# Pre-Amp_2017.net
KiCad netlist of a schematic drawn in Altium Designer
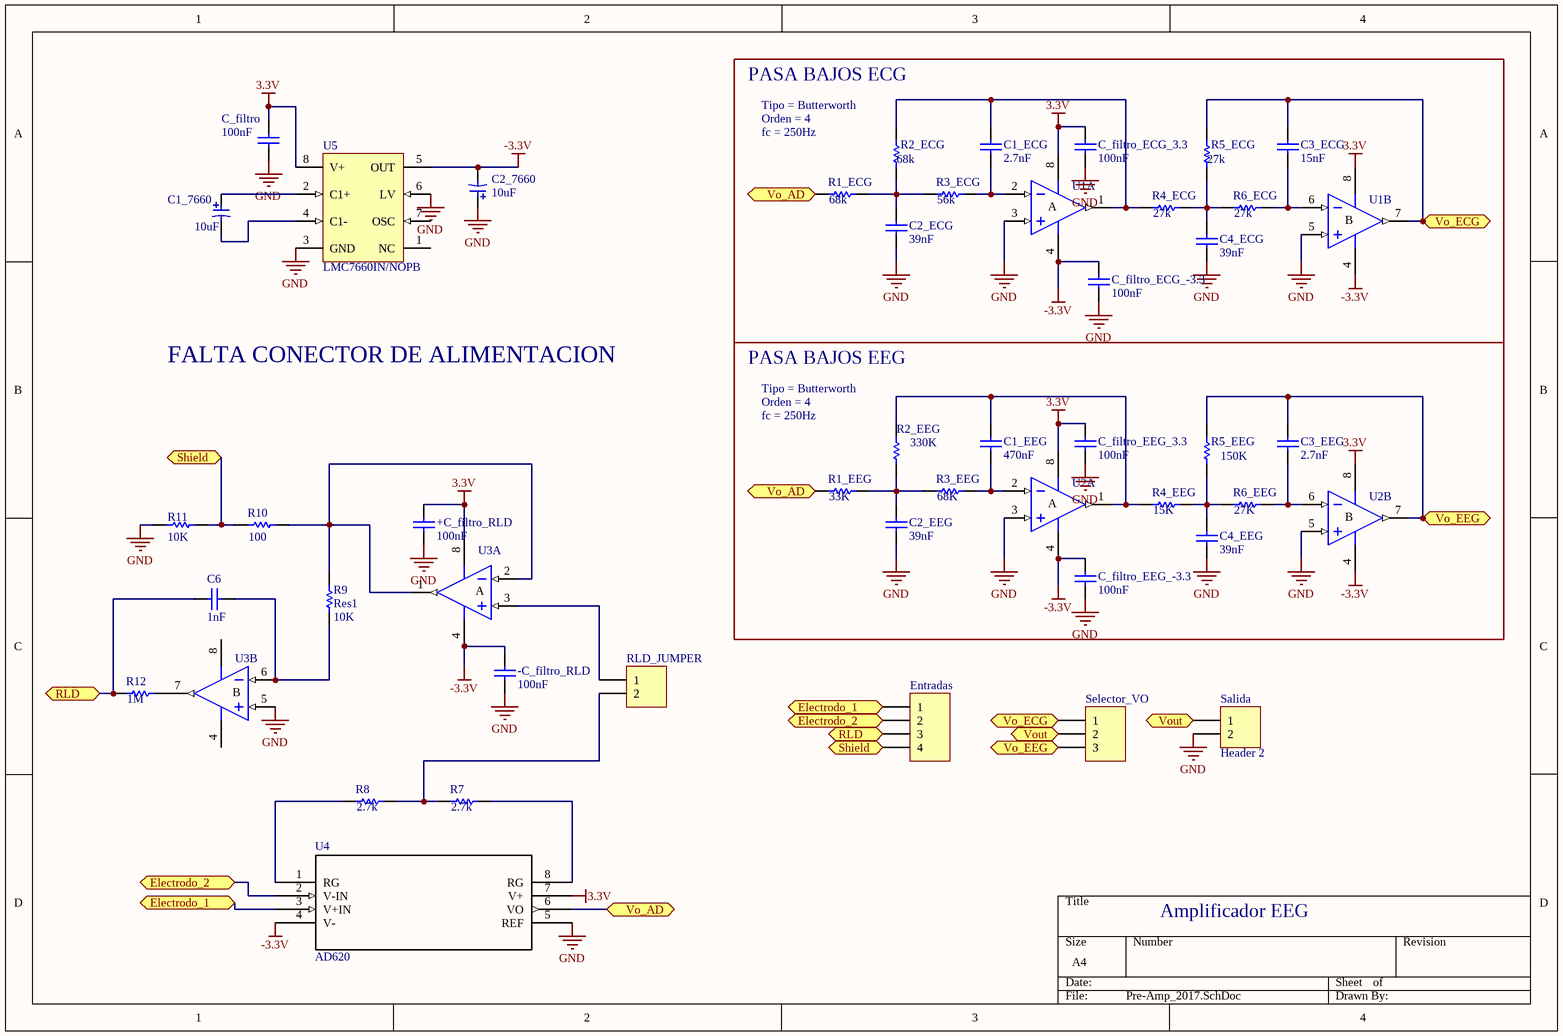
[diagram p0: Pre-Amp_2017.SchDoc]

(export (version "E")
  (design (tool "Eeschema 10.0.6"))
  (components
    (comp (ref "+C_filtro_RLD")
      (value "100nF")
      (footprint "VP40")
      (description "Dipped Radial Multilayer Ceramic Capacitor COG (NPO): 180pF, 50/63V")
      (fields (field (name "PUBLISHER") "Altium Limited"))
      (libsource (lib "Vishay Vitramon Ceramic Dipped Capacitor") (part "VP40BA181KA"))
    )
    (comp (ref "-C_filtro_RLD")
      (value "100nF")
      (footprint "VP40")
      (description "Dipped Radial Multilayer Ceramic Capacitor COG (NPO): 180pF, 50/63V")
      (fields (field (name "PUBLISHER") "Altium Limited"))
      (libsource (lib "Vishay Vitramon Ceramic Dipped Capacitor") (part "VP40BA181KA"))
    )
    (comp (ref "C1_7660")
      (value "10uF")
      (footprint "C Elec TH V 4x7-2.5")
      (description "Capacitor, polarized, generic")
      (fields (field (name "Comment") "C Pol"))
      (libsource (lib "IFS_Altium") (part "C Pol"))
    )
    (comp (ref "C1_ECG")
      (value "2.7nF")
      (footprint "VP40")
      (description "Dipped Radial Multilayer Ceramic Capacitor COG (NPO): 180pF, 50/63V")
      (fields (field (name "PUBLISHER") "Altium Limited"))
      (libsource (lib "Vishay Vitramon Ceramic Dipped Capacitor") (part "VP40BA181KA"))
    )
    (comp (ref "C1_EEG")
      (value "470nF")
      (footprint "VP40")
      (description "Dipped Radial Multilayer Ceramic Capacitor COG (NPO): 180pF, 50/63V")
      (fields (field (name "PUBLISHER") "Altium Limited"))
      (libsource (lib "Vishay Vitramon Ceramic Dipped Capacitor") (part "VP40BA181KA"))
    )
    (comp (ref "C2_7660")
      (value "10uF")
      (footprint "C Elec TH V 4x7-2.5")
      (description "Capacitor, polarized, generic")
      (fields (field (name "Comment") "C Pol"))
      (libsource (lib "IFS_Altium") (part "C Pol"))
    )
    (comp (ref "C2_ECG")
      (value "39nF")
      (footprint "VP40")
      (description "Dipped Radial Multilayer Ceramic Capacitor COG (NPO): 180pF, 50/63V")
      (fields (field (name "PUBLISHER") "Altium Limited"))
      (libsource (lib "Vishay Vitramon Ceramic Dipped Capacitor") (part "VP40BA181KA"))
    )
    (comp (ref "C2_EEG")
      (value "39nF")
      (footprint "VP40")
      (description "Dipped Radial Multilayer Ceramic Capacitor COG (NPO): 180pF, 50/63V")
      (fields (field (name "PUBLISHER") "Altium Limited"))
      (libsource (lib "Vishay Vitramon Ceramic Dipped Capacitor") (part "VP40BA181KA"))
    )
    (comp (ref "C3_ECG")
      (value "15nF")
      (footprint "VP40")
      (description "Dipped Radial Multilayer Ceramic Capacitor COG (NPO): 180pF, 50/63V")
      (fields (field (name "PUBLISHER") "Altium Limited"))
      (libsource (lib "Vishay Vitramon Ceramic Dipped Capacitor") (part "VP40BA181KA"))
    )
    (comp (ref "C3_EEG")
      (value "2.7nF")
      (footprint "VP40")
      (description "Dipped Radial Multilayer Ceramic Capacitor COG (NPO): 180pF, 50/63V")
      (fields (field (name "PUBLISHER") "Altium Limited"))
      (libsource (lib "Vishay Vitramon Ceramic Dipped Capacitor") (part "VP40BA181KA"))
    )
    (comp (ref "C4_ECG")
      (value "39nF")
      (footprint "VP40")
      (description "Dipped Radial Multilayer Ceramic Capacitor COG (NPO): 180pF, 50/63V")
      (fields (field (name "PUBLISHER") "Altium Limited"))
      (libsource (lib "Vishay Vitramon Ceramic Dipped Capacitor") (part "VP40BA181KA"))
    )
    (comp (ref "C4_EEG")
      (value "39nF")
      (footprint "VP40")
      (description "Dipped Radial Multilayer Ceramic Capacitor COG (NPO): 180pF, 50/63V")
      (fields (field (name "PUBLISHER") "Altium Limited"))
      (libsource (lib "Vishay Vitramon Ceramic Dipped Capacitor") (part "VP40BA181KA"))
    )
    (comp (ref "C6")
      (value "1nF")
      (footprint "VP40")
      (description "Dipped Radial Multilayer Ceramic Capacitor COG (NPO): 180pF, 50/63V")
      (fields (field (name "PUBLISHER") "Altium Limited"))
      (libsource (lib "Vishay Vitramon Ceramic Dipped Capacitor") (part "VP40BA181KA"))
    )
    (comp (ref "C_filtro")
      (value "100nF")
      (footprint "VP31-3.2")
      (description "Dipped Radial Multilayer Ceramic Capacitor COG (NPO): 82pF, 200V")
      (fields (field (name "PUBLISHER") "Altium Limited"))
      (libsource (lib "Vishay Vitramon Ceramic Dipped Capacitor") (part "VP31BA820KC"))
    )
    (comp (ref "C_filtro_ECG_-3.3")
      (value "100nF")
      (footprint "VP40")
      (description "Dipped Radial Multilayer Ceramic Capacitor COG (NPO): 180pF, 50/63V")
      (fields (field (name "PUBLISHER") "Altium Limited"))
      (libsource (lib "Vishay Vitramon Ceramic Dipped Capacitor") (part "VP40BA181KA"))
    )
    (comp (ref "C_filtro_ECG_3.3")
      (value "100nF")
      (footprint "VP40")
      (description "Dipped Radial Multilayer Ceramic Capacitor COG (NPO): 180pF, 50/63V")
      (fields (field (name "PUBLISHER") "Altium Limited"))
      (libsource (lib "Vishay Vitramon Ceramic Dipped Capacitor") (part "VP40BA181KA"))
    )
    (comp (ref "C_filtro_EEG_-3.3")
      (value "100nF")
      (footprint "VP40")
      (description "Dipped Radial Multilayer Ceramic Capacitor COG (NPO): 180pF, 50/63V")
      (fields (field (name "PUBLISHER") "Altium Limited"))
      (libsource (lib "Vishay Vitramon Ceramic Dipped Capacitor") (part "VP40BA181KA"))
    )
    (comp (ref "C_filtro_EEG_3.3")
      (value "100nF")
      (footprint "VP40")
      (description "Dipped Radial Multilayer Ceramic Capacitor COG (NPO): 180pF, 50/63V")
      (fields (field (name "PUBLISHER") "Altium Limited"))
      (libsource (lib "Vishay Vitramon Ceramic Dipped Capacitor") (part "VP40BA181KA"))
    )
    (comp (ref "Entradas")
      (value "Header 4")
      (footprint "HDR1X4")
      (description "Header, 4-Pin")
      (fields (field (name "PUBLISHER") "Altium Limited"))
      (libsource (lib "Miscellaneous Connectors") (part "Header 4"))
    )
    (comp (ref "R1_ECG")
      (value "68k")
      (footprint "AXIAL-0.3")
      (description "Resistor")
      (fields (field (name "Comment") "Res1") (field (name "PUBLISHER") "Altium Limited"))
      (libsource (lib "Miscellaneous Devices") (part "Res1"))
    )
    (comp (ref "R1_EEG")
      (value "33K")
      (footprint "AXIAL-0.3")
      (description "Resistor")
      (fields (field (name "Comment") "Res1") (field (name "PUBLISHER") "Altium Limited"))
      (libsource (lib "Miscellaneous Devices") (part "Res1"))
    )
    (comp (ref "R2_ECG")
      (value "68k")
      (footprint "AXIAL-0.3")
      (description "Resistor")
      (fields (field (name "Comment") "Res1") (field (name "PUBLISHER") "Altium Limited"))
      (libsource (lib "Miscellaneous Devices") (part "Res1"))
    )
    (comp (ref "R2_EEG")
      (value "330K")
      (footprint "AXIAL-0.3")
      (description "Resistor")
      (fields (field (name "Comment") "Res1") (field (name "PUBLISHER") "Altium Limited"))
      (libsource (lib "Miscellaneous Devices") (part "Res1"))
    )
    (comp (ref "R3_ECG")
      (value "56k")
      (footprint "AXIAL-0.3")
      (description "Resistor")
      (fields (field (name "Comment") "Res1") (field (name "PUBLISHER") "Altium Limited"))
      (libsource (lib "Miscellaneous Devices") (part "Res1"))
    )
    (comp (ref "R3_EEG")
      (value "68K")
      (footprint "AXIAL-0.3")
      (description "Resistor")
      (fields (field (name "Comment") "Res1") (field (name "PUBLISHER") "Altium Limited"))
      (libsource (lib "Miscellaneous Devices") (part "Res1"))
    )
    (comp (ref "R4_ECG")
      (value "27k")
      (footprint "AXIAL-0.3")
      (description "Resistor")
      (fields (field (name "Comment") "Res1") (field (name "PUBLISHER") "Altium Limited"))
      (libsource (lib "Miscellaneous Devices") (part "Res1"))
    )
    (comp (ref "R4_EEG")
      (value "15K")
      (footprint "AXIAL-0.3")
      (description "Resistor")
      (fields (field (name "Comment") "Res1") (field (name "PUBLISHER") "Altium Limited"))
      (libsource (lib "Miscellaneous Devices") (part "Res1"))
    )
    (comp (ref "R5_ECG")
      (value "27k")
      (footprint "AXIAL-0.3")
      (description "Resistor")
      (fields (field (name "Comment") "Res1") (field (name "PUBLISHER") "Altium Limited"))
      (libsource (lib "Miscellaneous Devices") (part "Res1"))
    )
    (comp (ref "R5_EEG")
      (value "150K")
      (footprint "AXIAL-0.3")
      (description "Resistor")
      (fields (field (name "Comment") "Res1") (field (name "PUBLISHER") "Altium Limited"))
      (libsource (lib "Miscellaneous Devices") (part "Res1"))
    )
    (comp (ref "R6_ECG")
      (value "27k")
      (footprint "AXIAL-0.3")
      (description "Resistor")
      (fields (field (name "Comment") "Res1") (field (name "PUBLISHER") "Altium Limited"))
      (libsource (lib "Miscellaneous Devices") (part "Res1"))
    )
    (comp (ref "R6_EEG")
      (value "27K")
      (footprint "AXIAL-0.3")
      (description "Resistor")
      (fields (field (name "Comment") "Res1") (field (name "PUBLISHER") "Altium Limited"))
      (libsource (lib "Miscellaneous Devices") (part "Res1"))
    )
    (comp (ref "R7")
      (value "2.7k")
      (footprint "AXIAL-0.3")
      (description "Resistor")
      (fields (field (name "Comment") "Res1") (field (name "PUBLISHER") "Altium Limited"))
      (libsource (lib "Miscellaneous Devices") (part "Res1"))
    )
    (comp (ref "R8")
      (value "2.7k")
      (footprint "AXIAL-0.3")
      (description "Resistor")
      (fields (field (name "Comment") "Res1") (field (name "PUBLISHER") "Altium Limited"))
      (libsource (lib "Miscellaneous Devices") (part "Res1"))
    )
    (comp (ref "R9")
      (value "Res1")
      (footprint "AXIAL-0.3")
      (description "Resistor")
      (fields (field (name "ALTIUM_VALUE") "10K") (field (name "PUBLISHER") "Altium Limited"))
      (libsource (lib "Miscellaneous Devices") (part "Res1"))
    )
    (comp (ref "R10")
      (value "100")
      (footprint "AXIAL-0.3")
      (description "Resistor")
      (fields (field (name "PUBLISHER") "Altium Limited"))
      (libsource (lib "Miscellaneous Devices") (part "Res1"))
    )
    (comp (ref "R11")
      (value "10K")
      (footprint "AXIAL-0.3")
      (description "Resistor")
      (fields (field (name "Comment") "Res1") (field (name "PUBLISHER") "Altium Limited"))
      (libsource (lib "Miscellaneous Devices") (part "Res1"))
    )
    (comp (ref "R12")
      (value "1M")
      (footprint "AXIAL-0.3")
      (description "Resistor")
      (fields (field (name "Comment") "Res1") (field (name "PUBLISHER") "Altium Limited"))
      (libsource (lib "Miscellaneous Devices") (part "Res1"))
    )
    (comp (ref "RLD_JUMPER")
      (value "Header 2")
      (footprint "HDR1X2")
      (description "Header, 2-Pin")
      (fields (field (name "PUBLISHER") "Altium Limited"))
      (libsource (lib "Miscellaneous Connectors") (part "Header 2"))
    )
    (comp (ref "Salida")
      (value "Header 2")
      (footprint "HDR1X2")
      (description "Header, 2-Pin")
      (fields (field (name "PUBLISHER") "Altium Limited"))
      (libsource (lib "Miscellaneous Connectors") (part "Header 2"))
    )
    (comp (ref "Selector_VO")
      (value "Header 3")
      (footprint "HDR1X3")
      (description "Header, 3-Pin")
      (fields (field (name "PUBLISHER") "Altium Limited"))
      (libsource (lib "Miscellaneous Connectors") (part "Header 3"))
    )
    (comp (ref "U1")
      (value "LT1358CN8")
      (footprint "N8")
      (description "Dual 25MHz, 600V/µs Operational Amplifier")
      (fields (field (name "PUBLISHER") "Altium Limited"))
      (libsource (lib "LT Operational Amplifier") (part "LT1358CN8"))
    )
    (comp (ref "U2")
      (value "LT1358CN8")
      (footprint "N8")
      (description "Dual 25MHz, 600V/µs Operational Amplifier")
      (fields (field (name "PUBLISHER") "Altium Limited"))
      (libsource (lib "LT Operational Amplifier") (part "LT1358CN8"))
    )
    (comp (ref "U3")
      (value "LT1358CN8")
      (footprint "N8")
      (description "Dual 25MHz, 600V/µs Operational Amplifier")
      (fields (field (name "PUBLISHER") "Altium Limited"))
      (libsource (lib "LT Operational Amplifier") (part "LT1358CN8"))
    )
    (comp (ref "U4") (value "AD620") (footprint "DIP8") (libsource (lib "Lucas") (part "INA129")))
    (comp (ref "U5")
      (value "LMC7660IN/NOPB")
      (footprint "N08E")
      (description "Switched Capacitor Voltage Converter, 8-pin MDIP, Pb-Free")
      (fields (field (name "MANUFACTURER") "National Semiconductor"))
      (libsource (lib "National Semiconductor Switch Caps") (part "LMC7660IN/NOPB"))
    )
  )
  (nets
    (net (code "1") (name "-3.3V") (class "Default")
      (node (ref "-C_filtro_RLD") (pin "2") (pinfunction "2_2") (pintype "passive"))
      (node (ref "C2_7660") (pin "1") (pinfunction "1_1") (pintype "passive"))
      (node (ref "C_filtro_ECG_-3.3") (pin "2") (pinfunction "2_2") (pintype "passive"))
      (node (ref "C_filtro_EEG_-3.3") (pin "2") (pinfunction "2_2") (pintype "passive"))
      (node (ref "U1") (pin "4") (pinfunction "V-_4") (pintype "power_in"))
      (node (ref "U2") (pin "4") (pinfunction "V-_4") (pintype "power_in"))
      (node (ref "U3") (pin "4") (pinfunction "V-_4") (pintype "power_in"))
      (node (ref "U4") (pin "4") (pinfunction "V-_4") (pintype "power_in"))
      (node (ref "U5") (pin "5") (pinfunction "OUT_5") (pintype "power_in"))
    )
    (net (code "2") (name "/Electrodo_1") (class "Default")
      (node (ref "Entradas") (pin "1") (pinfunction "1_1") (pintype "passive"))
      (node (ref "U4") (pin "3") (pinfunction "V+IN_3") (pintype "input"))
    )
    (net (code "3") (name "/Electrodo_2") (class "Default")
      (node (ref "Entradas") (pin "2") (pinfunction "2_2") (pintype "passive"))
      (node (ref "U4") (pin "2") (pinfunction "V-IN_2") (pintype "input"))
    )
    (net (code "4") (name "/RLD") (class "Default")
      (node (ref "C6") (pin "1") (pinfunction "1_1") (pintype "passive"))
      (node (ref "Entradas") (pin "3") (pinfunction "3_3") (pintype "passive"))
      (node (ref "R12") (pin "2") (pinfunction "2_2") (pintype "passive"))
    )
    (net (code "5") (name "/Shield") (class "Default")
      (node (ref "Entradas") (pin "4") (pinfunction "4_4") (pintype "passive"))
      (node (ref "R10") (pin "2") (pinfunction "2_2") (pintype "passive"))
      (node (ref "R11") (pin "1") (pinfunction "1_1") (pintype "passive"))
    )
    (net (code "6") (name "/Vo_AD") (class "Default")
      (node (ref "R1_ECG") (pin "1") (pinfunction "1_1") (pintype "passive"))
      (node (ref "R1_EEG") (pin "1") (pinfunction "1_1") (pintype "passive"))
      (node (ref "U4") (pin "6") (pinfunction "VO_6") (pintype "output"))
    )
    (net (code "7") (name "/Vo_ECG") (class "Default")
      (node (ref "C3_ECG") (pin "2") (pinfunction "2_2") (pintype "passive"))
      (node (ref "R5_ECG") (pin "2") (pinfunction "2_2") (pintype "passive"))
      (node (ref "Selector_VO") (pin "1") (pinfunction "1_1") (pintype "passive"))
      (node (ref "U1") (pin "7") (pinfunction "OUT_7") (pintype "output"))
    )
    (net (code "8") (name "/Vo_EEG") (class "Default")
      (node (ref "C3_EEG") (pin "2") (pinfunction "2_2") (pintype "passive"))
      (node (ref "R5_EEG") (pin "2") (pinfunction "2_2") (pintype "passive"))
      (node (ref "Selector_VO") (pin "3") (pinfunction "3_3") (pintype "passive"))
      (node (ref "U2") (pin "7") (pinfunction "OUT_7") (pintype "output"))
    )
    (net (code "9") (name "/Vout") (class "Default")
      (node (ref "Salida") (pin "1") (pinfunction "1_1") (pintype "passive"))
      (node (ref "Selector_VO") (pin "2") (pinfunction "2_2") (pintype "passive"))
    )
    (net (code "10") (name "3.3V") (class "Default")
      (node (ref "+C_filtro_RLD") (pin "2") (pinfunction "2_2") (pintype "passive"))
      (node (ref "C_filtro") (pin "2") (pinfunction "2_2") (pintype "passive"))
      (node (ref "C_filtro_ECG_3.3") (pin "2") (pinfunction "2_2") (pintype "passive"))
      (node (ref "C_filtro_EEG_3.3") (pin "2") (pinfunction "2_2") (pintype "passive"))
      (node (ref "U1") (pin "8") (pinfunction "V+_8") (pintype "power_in"))
      (node (ref "U2") (pin "8") (pinfunction "V+_8") (pintype "power_in"))
      (node (ref "U3") (pin "8") (pinfunction "V+_8") (pintype "power_in"))
      (node (ref "U4") (pin "7") (pinfunction "V+_7") (pintype "power_in"))
      (node (ref "U5") (pin "8") (pinfunction "V+_8") (pintype "power_in"))
    )
    (net (code "11") (name "GND") (class "Default")
      (node (ref "+C_filtro_RLD") (pin "1") (pinfunction "1_1") (pintype "passive"))
      (node (ref "-C_filtro_RLD") (pin "1") (pinfunction "1_1") (pintype "passive"))
      (node (ref "C2_7660") (pin "2") (pinfunction "2_2") (pintype "passive"))
      (node (ref "C2_ECG") (pin "1") (pinfunction "1_1") (pintype "passive"))
      (node (ref "C2_EEG") (pin "1") (pinfunction "1_1") (pintype "passive"))
      (node (ref "C4_ECG") (pin "1") (pinfunction "1_1") (pintype "passive"))
      (node (ref "C4_EEG") (pin "1") (pinfunction "1_1") (pintype "passive"))
      (node (ref "C_filtro") (pin "1") (pinfunction "1_1") (pintype "passive"))
      (node (ref "C_filtro_ECG_-3.3") (pin "1") (pinfunction "1_1") (pintype "passive"))
      (node (ref "C_filtro_ECG_3.3") (pin "1") (pinfunction "1_1") (pintype "passive"))
      (node (ref "C_filtro_EEG_-3.3") (pin "1") (pinfunction "1_1") (pintype "passive"))
      (node (ref "C_filtro_EEG_3.3") (pin "1") (pinfunction "1_1") (pintype "passive"))
      (node (ref "R11") (pin "2") (pinfunction "2_2") (pintype "passive"))
      (node (ref "Salida") (pin "2") (pinfunction "2_2") (pintype "passive"))
      (node (ref "U1") (pin "3") (pinfunction "IN+_3") (pintype "input"))
      (node (ref "U1") (pin "5") (pinfunction "IN+_5") (pintype "input"))
      (node (ref "U2") (pin "3") (pinfunction "IN+_3") (pintype "input"))
      (node (ref "U2") (pin "5") (pinfunction "IN+_5") (pintype "input"))
      (node (ref "U3") (pin "5") (pinfunction "IN+_5") (pintype "input"))
      (node (ref "U4") (pin "5") (pinfunction "REF_5") (pintype "passive"))
      (node (ref "U5") (pin "3") (pinfunction "GND_3") (pintype "power_in"))
      (node (ref "U5") (pin "6") (pinfunction "LV_6") (pintype "input"))
    )
    (net (code "12") (name "Net-(C2_ECG-Pad2)") (class "Default")
      (node (ref "C2_ECG") (pin "2") (pinfunction "2_2") (pintype "passive"))
      (node (ref "R1_ECG") (pin "2") (pinfunction "2_2") (pintype "passive"))
      (node (ref "R2_ECG") (pin "2") (pinfunction "2_2") (pintype "passive"))
      (node (ref "R3_ECG") (pin "1") (pinfunction "1_1") (pintype "passive"))
    )
    (net (code "13") (name "Net-(C2_EEG-Pad2)") (class "Default")
      (node (ref "C2_EEG") (pin "2") (pinfunction "2_2") (pintype "passive"))
      (node (ref "R1_EEG") (pin "2") (pinfunction "2_2") (pintype "passive"))
      (node (ref "R2_EEG") (pin "2") (pinfunction "2_2") (pintype "passive"))
      (node (ref "R3_EEG") (pin "1") (pinfunction "1_1") (pintype "passive"))
    )
    (net (code "14") (name "Net-(C4_ECG-Pad2)") (class "Default")
      (node (ref "C4_ECG") (pin "2") (pinfunction "2_2") (pintype "passive"))
      (node (ref "R4_ECG") (pin "2") (pinfunction "2_2") (pintype "passive"))
      (node (ref "R5_ECG") (pin "1") (pinfunction "1_1") (pintype "passive"))
      (node (ref "R6_ECG") (pin "2") (pinfunction "2_2") (pintype "passive"))
    )
    (net (code "15") (name "Net-(C4_EEG-Pad2)") (class "Default")
      (node (ref "C4_EEG") (pin "2") (pinfunction "2_2") (pintype "passive"))
      (node (ref "R4_EEG") (pin "2") (pinfunction "2_2") (pintype "passive"))
      (node (ref "R5_EEG") (pin "1") (pinfunction "1_1") (pintype "passive"))
      (node (ref "R6_EEG") (pin "2") (pinfunction "2_2") (pintype "passive"))
    )
    (net (code "16") (name "Net-(R7-Pad1)") (class "Default")
      (node (ref "R7") (pin "1") (pinfunction "1_1") (pintype "passive"))
      (node (ref "R8") (pin "2") (pinfunction "2_2") (pintype "passive"))
      (node (ref "RLD_JUMPER") (pin "2") (pinfunction "2_2") (pintype "passive"))
    )
    (net (code "17") (name "Net-(R7-Pad2)") (class "Default")
      (node (ref "R7") (pin "2") (pinfunction "2_2") (pintype "passive"))
      (node (ref "U4") (pin "8") (pinfunction "RG_8") (pintype "passive"))
    )
    (net (code "18") (name "Net-(R8-Pad1)") (class "Default")
      (node (ref "R8") (pin "1") (pinfunction "1_1") (pintype "passive"))
      (node (ref "U4") (pin "1") (pinfunction "RG_1") (pintype "passive"))
    )
    (net (code "19") (name "Net-(U1A-IN-)") (class "Default")
      (node (ref "C1_ECG") (pin "1") (pinfunction "1_1") (pintype "passive"))
      (node (ref "R3_ECG") (pin "2") (pinfunction "2_2") (pintype "passive"))
      (node (ref "U1") (pin "2") (pinfunction "IN-_2") (pintype "input"))
    )
    (net (code "20") (name "Net-(U1A-OUT)") (class "Default")
      (node (ref "C1_ECG") (pin "2") (pinfunction "2_2") (pintype "passive"))
      (node (ref "R2_ECG") (pin "1") (pinfunction "1_1") (pintype "passive"))
      (node (ref "R4_ECG") (pin "1") (pinfunction "1_1") (pintype "passive"))
      (node (ref "U1") (pin "1") (pinfunction "OUT_1") (pintype "output"))
    )
    (net (code "21") (name "Net-(U1B-IN-)") (class "Default")
      (node (ref "C3_ECG") (pin "1") (pinfunction "1_1") (pintype "passive"))
      (node (ref "R6_ECG") (pin "1") (pinfunction "1_1") (pintype "passive"))
      (node (ref "U1") (pin "6") (pinfunction "IN-_6") (pintype "input"))
    )
    (net (code "22") (name "Net-(U2A-IN-)") (class "Default")
      (node (ref "C1_EEG") (pin "1") (pinfunction "1_1") (pintype "passive"))
      (node (ref "R3_EEG") (pin "2") (pinfunction "2_2") (pintype "passive"))
      (node (ref "U2") (pin "2") (pinfunction "IN-_2") (pintype "input"))
    )
    (net (code "23") (name "Net-(U2A-OUT)") (class "Default")
      (node (ref "C1_EEG") (pin "2") (pinfunction "2_2") (pintype "passive"))
      (node (ref "R2_EEG") (pin "1") (pinfunction "1_1") (pintype "passive"))
      (node (ref "R4_EEG") (pin "1") (pinfunction "1_1") (pintype "passive"))
      (node (ref "U2") (pin "1") (pinfunction "OUT_1") (pintype "output"))
    )
    (net (code "24") (name "Net-(U2B-IN-)") (class "Default")
      (node (ref "C3_EEG") (pin "1") (pinfunction "1_1") (pintype "passive"))
      (node (ref "R6_EEG") (pin "1") (pinfunction "1_1") (pintype "passive"))
      (node (ref "U2") (pin "6") (pinfunction "IN-_6") (pintype "input"))
    )
    (net (code "25") (name "Net-(U3A-IN+)") (class "Default")
      (node (ref "RLD_JUMPER") (pin "1") (pinfunction "1_1") (pintype "passive"))
      (node (ref "U3") (pin "3") (pinfunction "IN+_3") (pintype "input"))
    )
    (net (code "26") (name "Net-(U3A-IN-)") (class "Default")
      (node (ref "R10") (pin "1") (pinfunction "1_1") (pintype "passive"))
      (node (ref "R9") (pin "2") (pinfunction "2_2") (pintype "passive"))
      (node (ref "U3") (pin "1") (pinfunction "OUT_1") (pintype "output"))
      (node (ref "U3") (pin "2") (pinfunction "IN-_2") (pintype "input"))
    )
    (net (code "27") (name "Net-(U3B-IN-)") (class "Default")
      (node (ref "C6") (pin "2") (pinfunction "2_2") (pintype "passive"))
      (node (ref "R9") (pin "1") (pinfunction "1_1") (pintype "passive"))
      (node (ref "U3") (pin "6") (pinfunction "IN-_6") (pintype "input"))
    )
    (net (code "28") (name "Net-(U3B-OUT)") (class "Default")
      (node (ref "R12") (pin "1") (pinfunction "1_1") (pintype "passive"))
      (node (ref "U3") (pin "7") (pinfunction "OUT_7") (pintype "output"))
    )
    (net (code "29") (name "Net-(U5-C1+)") (class "Default")
      (node (ref "C1_7660") (pin "2") (pinfunction "2_2") (pintype "passive"))
      (node (ref "U5") (pin "2") (pinfunction "C1+_2") (pintype "input"))
    )
    (net (code "30") (name "Net-(U5-C1-)") (class "Default")
      (node (ref "C1_7660") (pin "1") (pinfunction "1_1") (pintype "passive"))
      (node (ref "U5") (pin "4") (pinfunction "C1-_4") (pintype "input"))
    )
    (net (code "31") (name "unconnected-(U3B-V+-Pad8)") (class "Default")
      (node (ref "U3") (pin "8") (pinfunction "V+_8") (pintype "power_in"))
    )
    (net (code "32") (name "unconnected-(U3B-V--Pad4)") (class "Default")
      (node (ref "U3") (pin "4") (pinfunction "V-_4") (pintype "power_in"))
    )
    (net (code "33") (name "unconnected-(U5-NC-Pad1)") (class "Default")
      (node (ref "U5") (pin "1") (pinfunction "NC_1") (pintype "passive"))
    )
    (net (code "34") (name "unconnected-(U5-OSC-Pad7)") (class "Default")
      (node (ref "U5") (pin "7") (pinfunction "OSC_7") (pintype "input"))
    )
  )
)
